# cryptostick-0v2.net
KiCad netlist of a schematic drawn in EAGLE
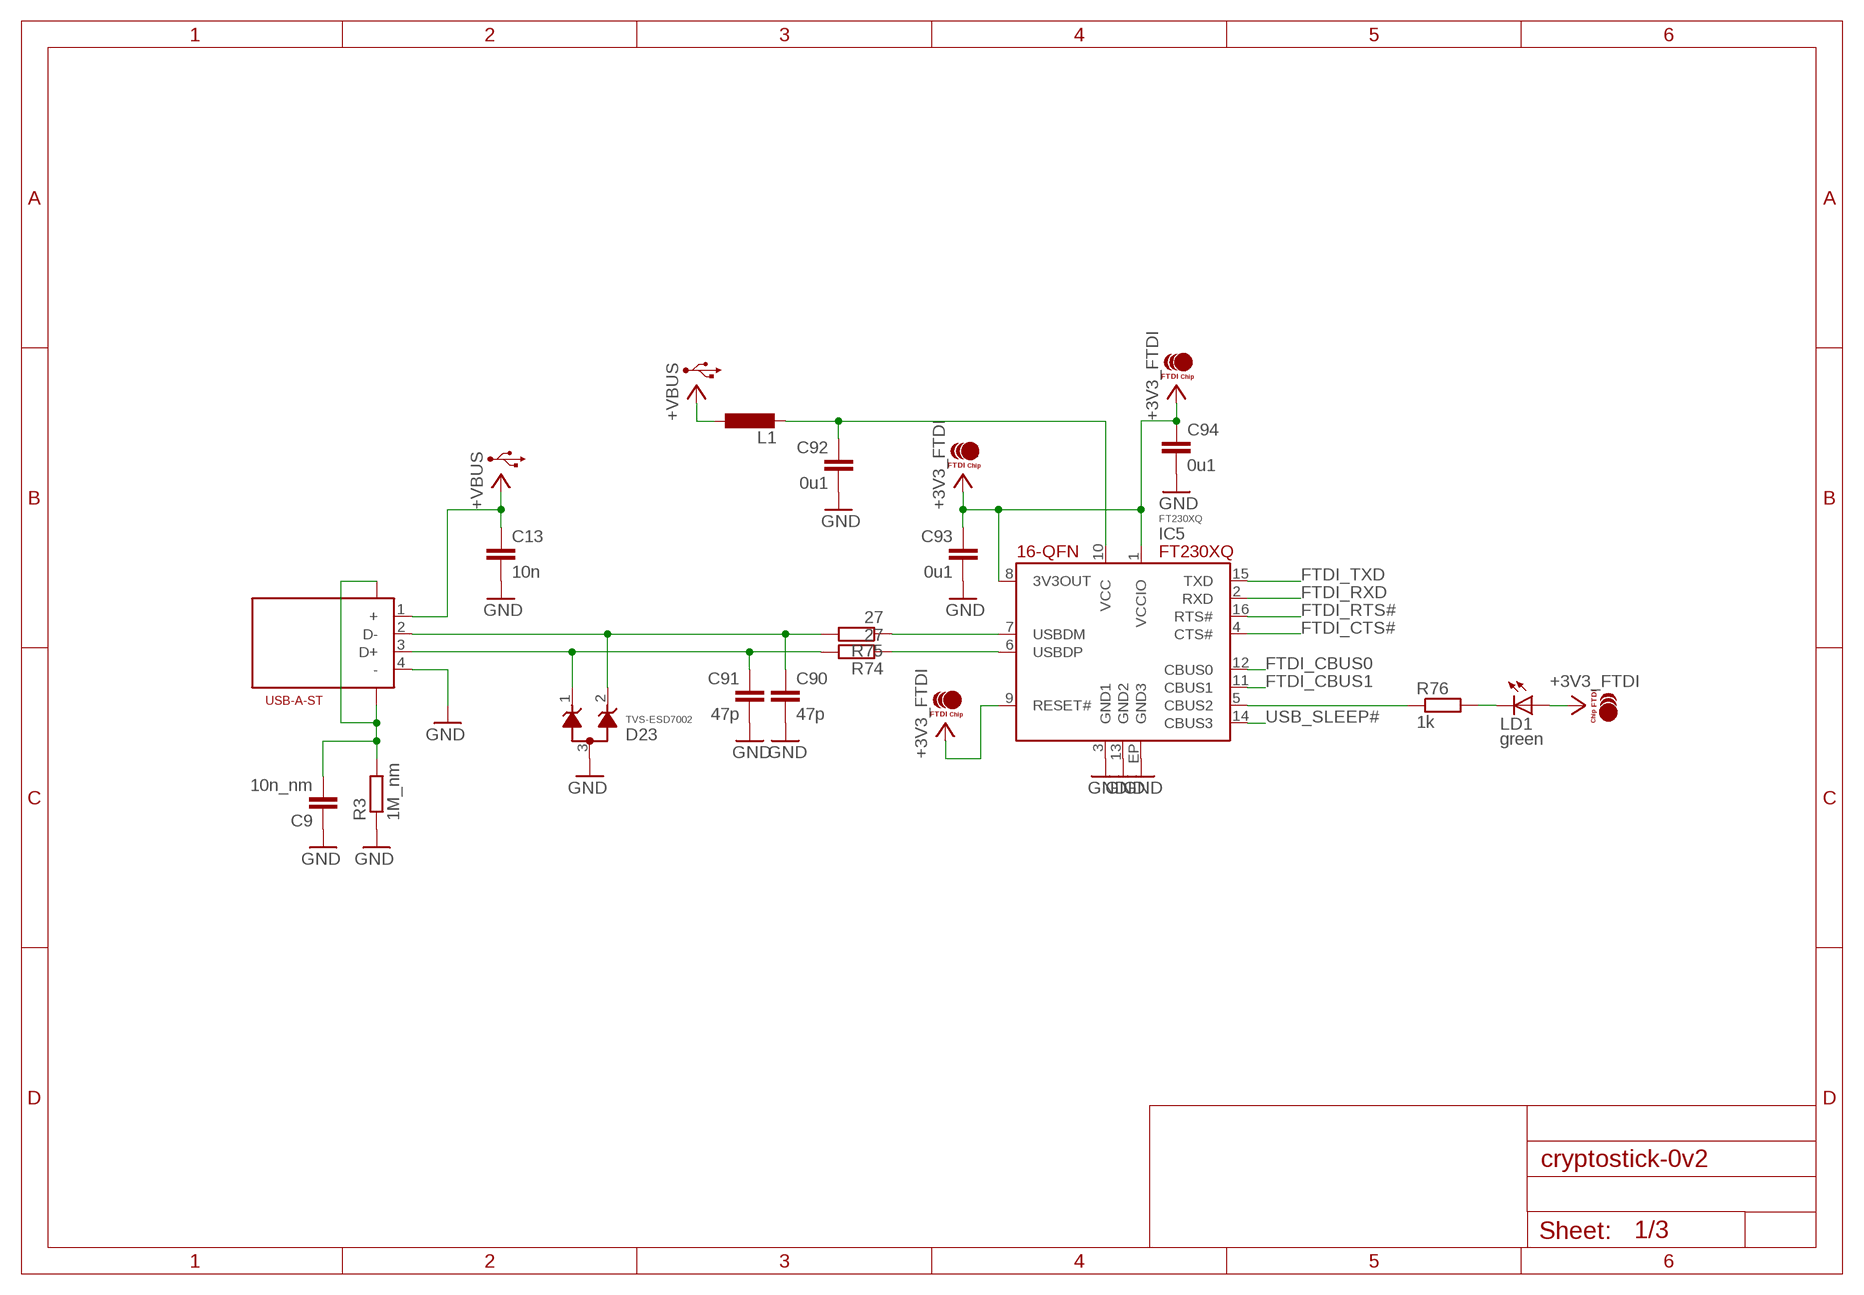
[diagram p0: schematic, sheet 1]
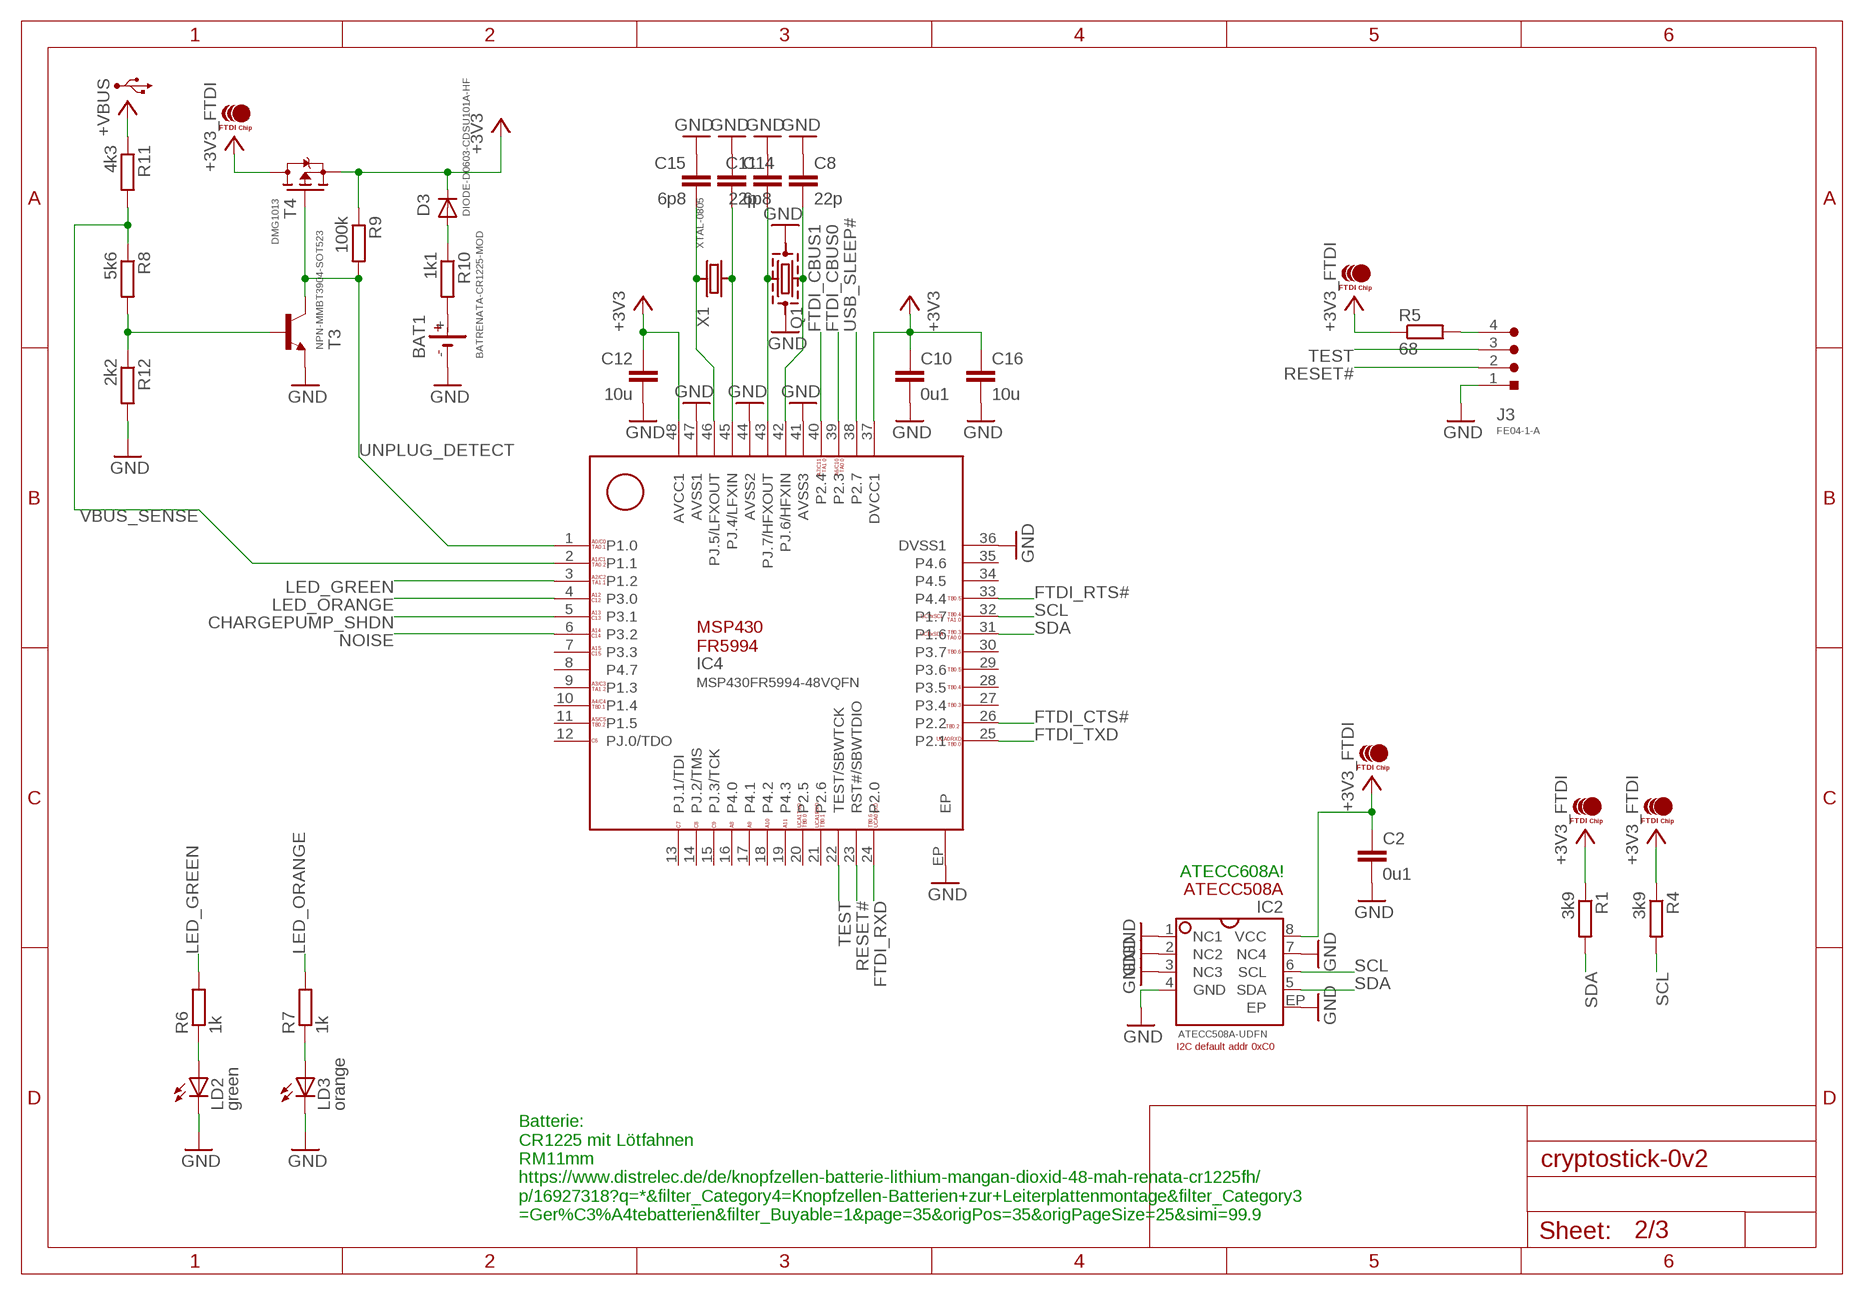
[diagram p1: schematic, sheet 2]
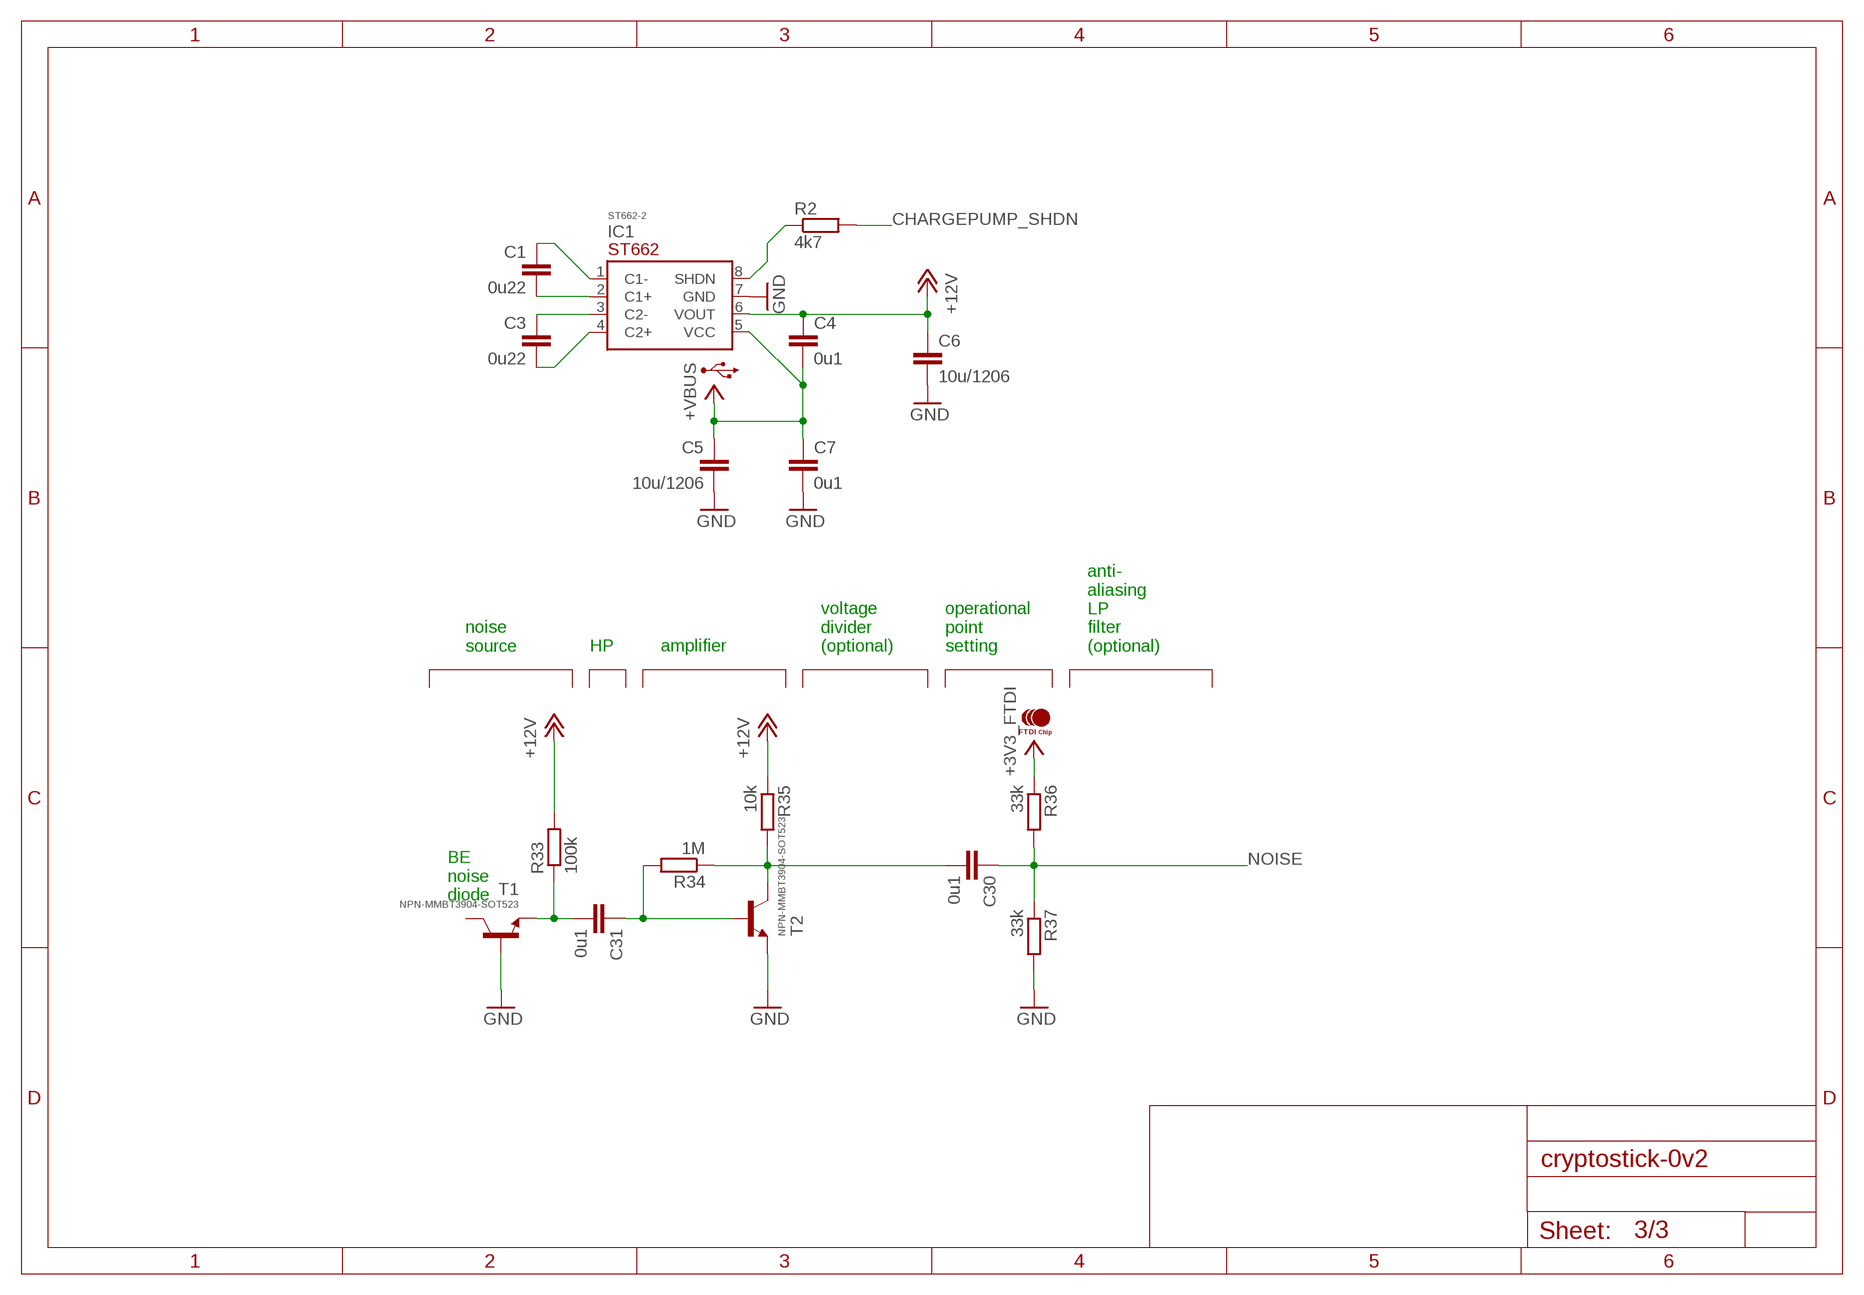
[diagram p2: schematic, sheet 3]

(export (version "E")
  (design (tool "Eeschema 10.0.6"))
  (components
    (comp (ref "C1")
      (value "0u22")
      (footprint "eagle-import:C0603")
      (libsource (lib "eagle-import") (part "C-EUC0603"))
    )
    (comp (ref "C3")
      (value "0u22")
      (footprint "eagle-import:C0603")
      (libsource (lib "eagle-import") (part "C-EUC0603"))
    )
    (comp (ref "C4")
      (value "0u1")
      (footprint "eagle-import:R0402-MCU")
      (libsource (lib "eagle-import") (part "C-EUR0402-MCU"))
    )
    (comp (ref "C5")
      (value "10u/1206")
      (footprint "eagle-import:C1206")
      (libsource (lib "eagle-import") (part "C-EUC1206"))
    )
    (comp (ref "C6")
      (value "10u/1206")
      (footprint "eagle-import:C1206")
      (libsource (lib "eagle-import") (part "C-EUC1206"))
    )
    (comp (ref "C7")
      (value "0u1")
      (footprint "eagle-import:R0402-MCU")
      (libsource (lib "eagle-import") (part "C-EUR0402-MCU"))
    )
    (comp (ref "C30")
      (value "0u1")
      (footprint "eagle-import:R0402-MCU")
      (libsource (lib "eagle-import") (part "C-EUR0402-MCU"))
    )
    (comp (ref "C31")
      (value "0u1")
      (footprint "eagle-import:R0402-MCU")
      (libsource (lib "eagle-import") (part "C-EUR0402-MCU"))
    )
    (comp (ref "IC1")
      (value "ST662-2")
      (footprint "eagle-import:8SOIC-2")
      (libsource (lib "eagle-import") (part "ST662-2"))
    )
    (comp (ref "R2")
      (value "4k7")
      (footprint "eagle-import:R0402-MCU")
      (libsource (lib "eagle-import") (part "R-EU_R0402-MCU"))
    )
    (comp (ref "R33")
      (value "100k")
      (footprint "eagle-import:R0402-MCU")
      (libsource (lib "eagle-import") (part "R-EU_R0402-MCU"))
    )
    (comp (ref "R34")
      (value "1M")
      (footprint "eagle-import:R0402-MCU")
      (libsource (lib "eagle-import") (part "R-EU_R0402-MCU"))
    )
    (comp (ref "R35")
      (value "10k")
      (footprint "eagle-import:R0402-MCU")
      (libsource (lib "eagle-import") (part "R-EU_R0402-MCU"))
    )
    (comp (ref "R36")
      (value "33k")
      (footprint "eagle-import:R0402-MCU")
      (libsource (lib "eagle-import") (part "R-EU_R0402-MCU"))
    )
    (comp (ref "R37")
      (value "33k")
      (footprint "eagle-import:R0402-MCU")
      (libsource (lib "eagle-import") (part "R-EU_R0402-MCU"))
    )
    (comp (ref "T1")
      (value "NPN-MMBT3904-SOT523")
      (footprint "eagle-import:SOT523")
      (libsource (lib "eagle-import") (part "NPN-MMBT3904-SOT523"))
    )
    (comp (ref "T2")
      (value "NPN-MMBT3904-SOT523")
      (footprint "eagle-import:SOT523")
      (libsource (lib "eagle-import") (part "NPN-MMBT3904-SOT523"))
    )
    (comp (ref "C9")
      (value "10n_nm")
      (footprint "eagle-import:C0603")
      (libsource (lib "eagle-import") (part "C-EUC0603"))
    )
    (comp (ref "C13")
      (value "10n")
      (footprint "eagle-import:R0402-MCU")
      (libsource (lib "eagle-import") (part "C-EUR0402-MCU"))
    )
    (comp (ref "C90")
      (value "47p")
      (footprint "eagle-import:R0402-MCU")
      (libsource (lib "eagle-import") (part "C-EUR0402-MCU"))
    )
    (comp (ref "C91")
      (value "47p")
      (footprint "eagle-import:R0402-MCU")
      (libsource (lib "eagle-import") (part "C-EUR0402-MCU"))
    )
    (comp (ref "C92")
      (value "0u1")
      (footprint "eagle-import:R0402-MCU")
      (libsource (lib "eagle-import") (part "C-EUR0402-MCU"))
    )
    (comp (ref "C93")
      (value "0u1")
      (footprint "eagle-import:R0402-MCU")
      (libsource (lib "eagle-import") (part "C-EUR0402-MCU"))
    )
    (comp (ref "C94")
      (value "0u1")
      (footprint "eagle-import:R0402-MCU")
      (libsource (lib "eagle-import") (part "C-EUR0402-MCU"))
    )
    (comp (ref "D23")
      (value "TVS-ESD7002")
      (footprint "eagle-import:SC70-3")
      (libsource (lib "eagle-import") (part "TVS-ESD7002"))
    )
    (comp (ref "IC5")
      (value "FT230XQ")
      (footprint "eagle-import:16QFN-FT230X")
      (libsource (lib "eagle-import") (part "FT230XQ"))
    )
    (comp (ref "J1")
      (value "USB-A-ST")
      (footprint "eagle-import:USB-A-ST")
      (libsource (lib "eagle-import") (part "USB-A-ST"))
    )
    (comp (ref "L1")
      (value "L-EUR0402-MCU")
      (footprint "eagle-import:R0402-MCU")
      (libsource (lib "eagle-import") (part "L-EUR0402-MCU"))
    )
    (comp (ref "LD1")
      (value "green")
      (footprint "eagle-import:0603-SIDELED-RPI")
      (libsource (lib "eagle-import") (part "LED-0603-SIDELED-RPI"))
    )
    (comp (ref "R3")
      (value "1M_nm")
      (footprint "eagle-import:R0603")
      (libsource (lib "eagle-import") (part "R-EU_R0603"))
    )
    (comp (ref "R74")
      (value "27")
      (footprint "eagle-import:R0402-MCU")
      (libsource (lib "eagle-import") (part "R-EU_R0402-MCU"))
    )
    (comp (ref "R75")
      (value "27")
      (footprint "eagle-import:R0402-MCU")
      (libsource (lib "eagle-import") (part "R-EU_R0402-MCU"))
    )
    (comp (ref "R76")
      (value "1k")
      (footprint "eagle-import:R0402-MCU")
      (libsource (lib "eagle-import") (part "R-EU_R0402-MCU"))
    )
    (comp (ref "BAT1")
      (value "BATRENATA-CR1225-MOD")
      (footprint "eagle-import:BAT-RENATA-CR1225-MOD")
      (libsource (lib "eagle-import") (part "BATRENATA-CR1225-MOD"))
    )
    (comp (ref "C2")
      (value "0u1")
      (footprint "eagle-import:R0402-MCU")
      (libsource (lib "eagle-import") (part "C-EUR0402-MCU"))
    )
    (comp (ref "C8")
      (value "22p")
      (footprint "eagle-import:R0402-MCU")
      (libsource (lib "eagle-import") (part "C-EUR0402-MCU"))
    )
    (comp (ref "C10")
      (value "0u1")
      (footprint "eagle-import:R0402-MCU")
      (libsource (lib "eagle-import") (part "C-EUR0402-MCU"))
    )
    (comp (ref "C11")
      (value "22p")
      (footprint "eagle-import:R0402-MCU")
      (libsource (lib "eagle-import") (part "C-EUR0402-MCU"))
    )
    (comp (ref "C12")
      (value "10u")
      (footprint "eagle-import:R0603-MCU")
      (libsource (lib "eagle-import") (part "C-EUR0603-MCU"))
    )
    (comp (ref "C14")
      (value "6p8")
      (footprint "eagle-import:R0402-MCU")
      (libsource (lib "eagle-import") (part "C-EUR0402-MCU"))
    )
    (comp (ref "C15")
      (value "6p8")
      (footprint "eagle-import:R0402-MCU")
      (libsource (lib "eagle-import") (part "C-EUR0402-MCU"))
    )
    (comp (ref "C16")
      (value "10u")
      (footprint "eagle-import:R0603-MCU")
      (libsource (lib "eagle-import") (part "C-EUR0603-MCU"))
    )
    (comp (ref "D3")
      (value "DIODE-D0603-CDSU101A-HF")
      (footprint "eagle-import:D-D0603")
      (libsource (lib "eagle-import") (part "DIODE-D0603"))
    )
    (comp (ref "IC2")
      (value "ATECC508A-UDFN")
      (footprint "eagle-import:8UDFN")
      (libsource (lib "eagle-import") (part "ATECC508A-UDFN"))
    )
    (comp (ref "IC4")
      (value "MSP430FR5994-48VQFN")
      (footprint "eagle-import:48VQFN-MSP430FR5994")
      (libsource (lib "eagle-import") (part "MSP430FR5994-48VQFN"))
    )
    (comp (ref "J3")
      (value "FE04-1-A")
      (footprint "eagle-import:FE04-1A")
      (libsource (lib "eagle-import") (part "FE04-1-A"))
    )
    (comp (ref "LD2")
      (value "green")
      (footprint "eagle-import:0603-SIDELED-RPI")
      (libsource (lib "eagle-import") (part "LED-0603-SIDELED-RPI"))
    )
    (comp (ref "LD3")
      (value "orange")
      (footprint "eagle-import:0603-SIDELED-RPI")
      (libsource (lib "eagle-import") (part "LED-0603-SIDELED-RPI"))
    )
    (comp (ref "Q1")
      (value "XTAL-2.0X1.6-MOD")
      (footprint "eagle-import:XTAL-2.0X1.6-MOD")
      (libsource (lib "eagle-import") (part "XTAL-2.0X1.6-MOD"))
    )
    (comp (ref "R1")
      (value "3k9")
      (footprint "eagle-import:R0402-MCU")
      (libsource (lib "eagle-import") (part "R-EU_R0402-MCU"))
    )
    (comp (ref "R4")
      (value "3k9")
      (footprint "eagle-import:R0402-MCU")
      (libsource (lib "eagle-import") (part "R-EU_R0402-MCU"))
    )
    (comp (ref "R5")
      (value "68")
      (footprint "eagle-import:R0402-MCU")
      (libsource (lib "eagle-import") (part "R-EU_R0402-MCU"))
    )
    (comp (ref "R6")
      (value "1k")
      (footprint "eagle-import:R0402-MCU")
      (libsource (lib "eagle-import") (part "R-EU_R0402-MCU"))
    )
    (comp (ref "R7")
      (value "1k")
      (footprint "eagle-import:R0402-MCU")
      (libsource (lib "eagle-import") (part "R-EU_R0402-MCU"))
    )
    (comp (ref "R8")
      (value "5k6")
      (footprint "eagle-import:R0402-MCU")
      (libsource (lib "eagle-import") (part "R-EU_R0402-MCU"))
    )
    (comp (ref "R9")
      (value "100k")
      (footprint "eagle-import:R0402-MCU")
      (libsource (lib "eagle-import") (part "R-EU_R0402-MCU"))
    )
    (comp (ref "R10")
      (value "1k1")
      (footprint "eagle-import:R0402-MCU")
      (libsource (lib "eagle-import") (part "R-EU_R0402-MCU"))
    )
    (comp (ref "R11")
      (value "4k3")
      (footprint "eagle-import:R0402-MCU")
      (libsource (lib "eagle-import") (part "R-EU_R0402-MCU"))
    )
    (comp (ref "R12")
      (value "2k2")
      (footprint "eagle-import:R0402-MCU")
      (libsource (lib "eagle-import") (part "R-EU_R0402-MCU"))
    )
    (comp (ref "T3")
      (value "NPN-MMBT3904-SOT523")
      (footprint "eagle-import:SOT523")
      (libsource (lib "eagle-import") (part "NPN-MMBT3904-SOT523"))
    )
    (comp (ref "T4")
      (value "DMG1013")
      (footprint "eagle-import:SC70-3")
      (libsource (lib "eagle-import") (part "P-MOSFET-SC70-3"))
    )
    (comp (ref "X1")
      (value "XTAL-0805")
      (footprint "eagle-import:XTAL-32KHZ-0805")
      (libsource (lib "eagle-import") (part "XTAL-0805"))
    )
  )
  (nets
    (net (code "1") (name "+3V3") (class "Default")
      (node (ref "C10") (pin "1") (pinfunction "1_1") (pintype "passive"))
      (node (ref "C12") (pin "1") (pinfunction "1_1") (pintype "passive"))
      (node (ref "C16") (pin "1") (pinfunction "1_1") (pintype "passive"))
      (node (ref "D3") (pin "C") (pinfunction "C_C") (pintype "bidirectional"))
      (node (ref "IC4") (pin "37") (pinfunction "DVCC1_37") (pintype "power_in"))
      (node (ref "IC4") (pin "48") (pinfunction "AVCC1_48") (pintype "power_in"))
      (node (ref "R9") (pin "1") (pinfunction "1_1") (pintype "passive"))
      (node (ref "T4") (pin "2") (pinfunction "S_2") (pintype "passive"))
    )
    (net (code "2") (name "+3V3_FTDI") (class "Default")
      (node (ref "C2") (pin "1") (pinfunction "1_1") (pintype "passive"))
      (node (ref "C93") (pin "1") (pinfunction "1_1") (pintype "passive"))
      (node (ref "C94") (pin "1") (pinfunction "1_1") (pintype "passive"))
      (node (ref "IC2") (pin "8") (pinfunction "VCC_8") (pintype "bidirectional"))
      (node (ref "IC5") (pin "1") (pinfunction "VCCIO_1") (pintype "bidirectional"))
      (node (ref "IC5") (pin "8") (pinfunction "3V3OUT_8") (pintype "bidirectional"))
      (node (ref "IC5") (pin "9") (pinfunction "RESET#_9") (pintype "bidirectional"))
      (node (ref "LD1") (pin "A") (pinfunction "A_A") (pintype "passive"))
      (node (ref "R1") (pin "1") (pinfunction "1_1") (pintype "passive"))
      (node (ref "R36") (pin "1") (pinfunction "1_1") (pintype "passive"))
      (node (ref "R4") (pin "1") (pinfunction "1_1") (pintype "passive"))
      (node (ref "R5") (pin "1") (pinfunction "1_1") (pintype "passive"))
      (node (ref "T4") (pin "3") (pinfunction "D_3") (pintype "passive"))
    )
    (net (code "3") (name "+12V") (class "Default")
      (node (ref "C4") (pin "1") (pinfunction "1_1") (pintype "passive"))
      (node (ref "C6") (pin "1") (pinfunction "1_1") (pintype "passive"))
      (node (ref "IC1") (pin "6") (pinfunction "VOUT_6") (pintype "bidirectional"))
      (node (ref "R33") (pin "2") (pinfunction "2_2") (pintype "passive"))
      (node (ref "R35") (pin "1") (pinfunction "1_1") (pintype "passive"))
    )
    (net (code "4") (name "+VBUS") (class "Default")
      (node (ref "C13") (pin "1") (pinfunction "1_1") (pintype "passive"))
      (node (ref "C4") (pin "2") (pinfunction "2_2") (pintype "passive"))
      (node (ref "C5") (pin "1") (pinfunction "1_1") (pintype "passive"))
      (node (ref "C7") (pin "1") (pinfunction "1_1") (pintype "passive"))
      (node (ref "IC1") (pin "5") (pinfunction "VCC_5") (pintype "bidirectional"))
      (node (ref "J1") (pin "1") (pinfunction "+_1") (pintype "bidirectional"))
      (node (ref "L1") (pin "1") (pinfunction "1_1") (pintype "passive"))
      (node (ref "R11") (pin "1") (pinfunction "1_1") (pintype "passive"))
    )
    (net (code "5") (name "CHARGEPUMP_SHDN") (class "Default")
      (node (ref "IC4") (pin "5") (pinfunction "P3.1_5") (pintype "bidirectional"))
      (node (ref "R2") (pin "2") (pinfunction "2_2") (pintype "passive"))
    )
    (net (code "6") (name "FTDI_CBUS0") (class "Default")
      (node (ref "IC4") (pin "39") (pinfunction "P2.3_39") (pintype "bidirectional"))
      (node (ref "IC5") (pin "12") (pinfunction "CBUS0_12") (pintype "bidirectional"))
    )
    (net (code "7") (name "FTDI_CBUS1") (class "Default")
      (node (ref "IC4") (pin "40") (pinfunction "P2.4_40") (pintype "bidirectional"))
      (node (ref "IC5") (pin "11") (pinfunction "CBUS1_11") (pintype "bidirectional"))
    )
    (net (code "8") (name "FTDI_CTS#") (class "Default")
      (node (ref "IC4") (pin "26") (pinfunction "P2.2_26") (pintype "bidirectional"))
      (node (ref "IC5") (pin "4") (pinfunction "CTS#_4") (pintype "bidirectional"))
    )
    (net (code "9") (name "FTDI_RTS#") (class "Default")
      (node (ref "IC4") (pin "33") (pinfunction "P4.4_33") (pintype "bidirectional"))
      (node (ref "IC5") (pin "16") (pinfunction "RTS#_16") (pintype "bidirectional"))
    )
    (net (code "10") (name "FTDI_RXD") (class "Default")
      (node (ref "IC4") (pin "24") (pinfunction "P2.0_24") (pintype "bidirectional"))
      (node (ref "IC5") (pin "2") (pinfunction "RXD_2") (pintype "bidirectional"))
    )
    (net (code "11") (name "FTDI_TXD") (class "Default")
      (node (ref "IC4") (pin "25") (pinfunction "P2.1_25") (pintype "bidirectional"))
      (node (ref "IC5") (pin "15") (pinfunction "TXD_15") (pintype "bidirectional"))
    )
    (net (code "12") (name "GND") (class "Default")
      (node (ref "BAT1") (pin "-") (pinfunction "-_-") (pintype "bidirectional"))
      (node (ref "C10") (pin "2") (pinfunction "2_2") (pintype "passive"))
      (node (ref "C11") (pin "1") (pinfunction "1_1") (pintype "passive"))
      (node (ref "C12") (pin "2") (pinfunction "2_2") (pintype "passive"))
      (node (ref "C13") (pin "2") (pinfunction "2_2") (pintype "passive"))
      (node (ref "C14") (pin "1") (pinfunction "1_1") (pintype "passive"))
      (node (ref "C15") (pin "1") (pinfunction "1_1") (pintype "passive"))
      (node (ref "C16") (pin "2") (pinfunction "2_2") (pintype "passive"))
      (node (ref "C2") (pin "2") (pinfunction "2_2") (pintype "passive"))
      (node (ref "C5") (pin "2") (pinfunction "2_2") (pintype "passive"))
      (node (ref "C6") (pin "2") (pinfunction "2_2") (pintype "passive"))
      (node (ref "C7") (pin "2") (pinfunction "2_2") (pintype "passive"))
      (node (ref "C8") (pin "1") (pinfunction "1_1") (pintype "passive"))
      (node (ref "C9") (pin "1") (pinfunction "1_1") (pintype "passive"))
      (node (ref "C90") (pin "2") (pinfunction "2_2") (pintype "passive"))
      (node (ref "C91") (pin "2") (pinfunction "2_2") (pintype "passive"))
      (node (ref "C92") (pin "2") (pinfunction "2_2") (pintype "passive"))
      (node (ref "C93") (pin "2") (pinfunction "2_2") (pintype "passive"))
      (node (ref "C94") (pin "2") (pinfunction "2_2") (pintype "passive"))
      (node (ref "D23") (pin "3") (pinfunction "3_3") (pintype "bidirectional"))
      (node (ref "IC1") (pin "7") (pinfunction "GND_7") (pintype "bidirectional"))
      (node (ref "IC2") (pin "1") (pinfunction "NC1_1") (pintype "bidirectional"))
      (node (ref "IC2") (pin "2") (pinfunction "NC2_2") (pintype "bidirectional"))
      (node (ref "IC2") (pin "3") (pinfunction "NC3_3") (pintype "bidirectional"))
      (node (ref "IC2") (pin "4") (pinfunction "GND_4") (pintype "bidirectional"))
      (node (ref "IC2") (pin "7") (pinfunction "NC4_7") (pintype "bidirectional"))
      (node (ref "IC2") (pin "EP") (pinfunction "EP_EP") (pintype "bidirectional"))
      (node (ref "IC4") (pin "36") (pinfunction "DVSS1_36") (pintype "power_in"))
      (node (ref "IC4") (pin "41") (pinfunction "AVSS3_41") (pintype "power_in"))
      (node (ref "IC4") (pin "44") (pinfunction "AVSS2_44") (pintype "power_in"))
      (node (ref "IC4") (pin "47") (pinfunction "AVSS1_47") (pintype "power_in"))
      (node (ref "IC4") (pin "EP") (pinfunction "EP_EP") (pintype "bidirectional"))
      (node (ref "IC5") (pin "13") (pinfunction "GND2_13") (pintype "bidirectional"))
      (node (ref "IC5") (pin "3") (pinfunction "GND1_3") (pintype "bidirectional"))
      (node (ref "IC5") (pin "EP") (pinfunction "GND3_EP") (pintype "bidirectional"))
      (node (ref "J1") (pin "4") (pinfunction "-_4") (pintype "bidirectional"))
      (node (ref "J3") (pin "1") (pinfunction "1_1") (pintype "bidirectional"))
      (node (ref "LD2") (pin "C") (pinfunction "C_C") (pintype "passive"))
      (node (ref "LD3") (pin "C") (pinfunction "C_C") (pintype "passive"))
      (node (ref "Q1") (pin "2") (pinfunction "GND1_2") (pintype "bidirectional"))
      (node (ref "Q1") (pin "4") (pinfunction "GND2_4") (pintype "bidirectional"))
      (node (ref "R12") (pin "2") (pinfunction "2_2") (pintype "passive"))
      (node (ref "R3") (pin "1") (pinfunction "1_1") (pintype "passive"))
      (node (ref "R37") (pin "2") (pinfunction "2_2") (pintype "passive"))
      (node (ref "T1") (pin "1") (pinfunction "B_1") (pintype "passive"))
      (node (ref "T2") (pin "2") (pinfunction "E_2") (pintype "passive"))
      (node (ref "T3") (pin "2") (pinfunction "E_2") (pintype "passive"))
    )
    (net (code "13") (name "LED_GREEN") (class "Default")
      (node (ref "IC4") (pin "3") (pinfunction "P1.2_3") (pintype "bidirectional"))
      (node (ref "R6") (pin "2") (pinfunction "2_2") (pintype "passive"))
    )
    (net (code "14") (name "LED_ORANGE") (class "Default")
      (node (ref "IC4") (pin "4") (pinfunction "P3.0_4") (pintype "bidirectional"))
      (node (ref "R7") (pin "2") (pinfunction "2_2") (pintype "passive"))
    )
    (net (code "15") (name "NOISE") (class "Default")
      (node (ref "C30") (pin "1") (pinfunction "1_1") (pintype "passive"))
      (node (ref "IC4") (pin "6") (pinfunction "P3.2_6") (pintype "bidirectional"))
      (node (ref "R36") (pin "2") (pinfunction "2_2") (pintype "passive"))
      (node (ref "R37") (pin "1") (pinfunction "1_1") (pintype "passive"))
    )
    (net (code "16") (name "Net-(BAT1-Pad+)") (class "Default")
      (node (ref "BAT1") (pin "+") (pinfunction "+_+") (pintype "bidirectional"))
      (node (ref "R10") (pin "2") (pinfunction "2_2") (pintype "passive"))
    )
    (net (code "17") (name "Net-(C9-Pad2)") (class "Default")
      (node (ref "C9") (pin "2") (pinfunction "2_2") (pintype "passive"))
      (node (ref "J1") (pin "SH1") (pinfunction "SH1_SH1") (pintype "bidirectional"))
      (node (ref "J1") (pin "SH2") (pinfunction "SH2_SH2") (pintype "bidirectional"))
      (node (ref "R3") (pin "2") (pinfunction "2_2") (pintype "passive"))
    )
    (net (code "18") (name "Net-(D3-PadA)") (class "Default")
      (node (ref "D3") (pin "A") (pinfunction "A_A") (pintype "bidirectional"))
      (node (ref "R10") (pin "1") (pinfunction "1_1") (pintype "passive"))
    )
    (net (code "19") (name "Net-(IC1-C1+)") (class "Default")
      (node (ref "C1") (pin "2") (pinfunction "2_2") (pintype "passive"))
      (node (ref "IC1") (pin "2") (pinfunction "C1+_2") (pintype "bidirectional"))
    )
    (net (code "20") (name "Net-(IC1-C1-)") (class "Default")
      (node (ref "C1") (pin "1") (pinfunction "1_1") (pintype "passive"))
      (node (ref "IC1") (pin "1") (pinfunction "C1-_1") (pintype "bidirectional"))
    )
    (net (code "21") (name "Net-(IC1-C2+)") (class "Default")
      (node (ref "C3") (pin "2") (pinfunction "2_2") (pintype "passive"))
      (node (ref "IC1") (pin "4") (pinfunction "C2+_4") (pintype "bidirectional"))
    )
    (net (code "22") (name "Net-(IC1-C2-)") (class "Default")
      (node (ref "C3") (pin "1") (pinfunction "1_1") (pintype "passive"))
      (node (ref "IC1") (pin "3") (pinfunction "C2-_3") (pintype "bidirectional"))
    )
    (net (code "23") (name "Net-(IC1-SHDN)") (class "Default")
      (node (ref "IC1") (pin "8") (pinfunction "SHDN_8") (pintype "bidirectional"))
      (node (ref "R2") (pin "1") (pinfunction "1_1") (pintype "passive"))
    )
    (net (code "24") (name "Net-(IC4-PJ.4{slash}LFXIN)") (class "Default")
      (node (ref "C14") (pin "2") (pinfunction "2_2") (pintype "passive"))
      (node (ref "IC4") (pin "45") (pinfunction "PJ.4/LFXIN_45") (pintype "bidirectional"))
      (node (ref "X1") (pin "P$1") (pinfunction "1_P$1") (pintype "bidirectional"))
    )
    (net (code "25") (name "Net-(IC4-PJ.5{slash}LFXOUT)") (class "Default")
      (node (ref "C15") (pin "2") (pinfunction "2_2") (pintype "passive"))
      (node (ref "IC4") (pin "46") (pinfunction "PJ.5/LFXOUT_46") (pintype "bidirectional"))
      (node (ref "X1") (pin "P$2") (pinfunction "2_P$2") (pintype "bidirectional"))
    )
    (net (code "26") (name "Net-(IC4-PJ.6{slash}HFXIN)") (class "Default")
      (node (ref "C8") (pin "2") (pinfunction "2_2") (pintype "passive"))
      (node (ref "IC4") (pin "42") (pinfunction "PJ.6/HFXIN_42") (pintype "bidirectional"))
      (node (ref "Q1") (pin "3") (pinfunction "2_3") (pintype "bidirectional"))
    )
    (net (code "27") (name "Net-(IC4-PJ.7{slash}HFXOUT)") (class "Default")
      (node (ref "C11") (pin "2") (pinfunction "2_2") (pintype "passive"))
      (node (ref "IC4") (pin "43") (pinfunction "PJ.7/HFXOUT_43") (pintype "bidirectional"))
      (node (ref "Q1") (pin "1") (pinfunction "1_1") (pintype "bidirectional"))
    )
    (net (code "28") (name "Net-(IC5-CBUS2)") (class "Default")
      (node (ref "IC5") (pin "5") (pinfunction "CBUS2_5") (pintype "bidirectional"))
      (node (ref "R76") (pin "1") (pinfunction "1_1") (pintype "passive"))
    )
    (net (code "29") (name "Net-(IC5-USBDM)") (class "Default")
      (node (ref "IC5") (pin "7") (pinfunction "USBDM_7") (pintype "bidirectional"))
      (node (ref "R75") (pin "1") (pinfunction "1_1") (pintype "passive"))
    )
    (net (code "30") (name "Net-(IC5-USBDP)") (class "Default")
      (node (ref "IC5") (pin "6") (pinfunction "USBDP_6") (pintype "bidirectional"))
      (node (ref "R74") (pin "1") (pinfunction "1_1") (pintype "passive"))
    )
    (net (code "31") (name "Net-(IC5-VCC)") (class "Default")
      (node (ref "C92") (pin "1") (pinfunction "1_1") (pintype "passive"))
      (node (ref "IC5") (pin "10") (pinfunction "VCC_10") (pintype "bidirectional"))
      (node (ref "L1") (pin "2") (pinfunction "2_2") (pintype "passive"))
    )
    (net (code "32") (name "Net-(J1-D+)") (class "Default")
      (node (ref "C91") (pin "1") (pinfunction "1_1") (pintype "passive"))
      (node (ref "D23") (pin "1") (pinfunction "1_1") (pintype "bidirectional"))
      (node (ref "J1") (pin "3") (pinfunction "D+_3") (pintype "bidirectional"))
      (node (ref "R74") (pin "2") (pinfunction "2_2") (pintype "passive"))
    )
    (net (code "33") (name "Net-(J1-D-)") (class "Default")
      (node (ref "C90") (pin "1") (pinfunction "1_1") (pintype "passive"))
      (node (ref "D23") (pin "2") (pinfunction "2_2") (pintype "bidirectional"))
      (node (ref "J1") (pin "2") (pinfunction "D-_2") (pintype "bidirectional"))
      (node (ref "R75") (pin "2") (pinfunction "2_2") (pintype "passive"))
    )
    (net (code "34") (name "Net-(J3-Pad4)") (class "Default")
      (node (ref "J3") (pin "4") (pinfunction "4_4") (pintype "bidirectional"))
      (node (ref "R5") (pin "2") (pinfunction "2_2") (pintype "passive"))
    )
    (net (code "35") (name "Net-(LD1-PadC)") (class "Default")
      (node (ref "LD1") (pin "C") (pinfunction "C_C") (pintype "passive"))
      (node (ref "R76") (pin "2") (pinfunction "2_2") (pintype "passive"))
    )
    (net (code "36") (name "Net-(LD2-PadA)") (class "Default")
      (node (ref "LD2") (pin "A") (pinfunction "A_A") (pintype "passive"))
      (node (ref "R6") (pin "1") (pinfunction "1_1") (pintype "passive"))
    )
    (net (code "37") (name "Net-(LD3-PadA)") (class "Default")
      (node (ref "LD3") (pin "A") (pinfunction "A_A") (pintype "passive"))
      (node (ref "R7") (pin "1") (pinfunction "1_1") (pintype "passive"))
    )
    (net (code "38") (name "Net-(T1-E)") (class "Default")
      (node (ref "C31") (pin "2") (pinfunction "2_2") (pintype "passive"))
      (node (ref "R33") (pin "1") (pinfunction "1_1") (pintype "passive"))
      (node (ref "T1") (pin "2") (pinfunction "E_2") (pintype "passive"))
    )
    (net (code "39") (name "Net-(T2-B)") (class "Default")
      (node (ref "C31") (pin "1") (pinfunction "1_1") (pintype "passive"))
      (node (ref "R34") (pin "2") (pinfunction "2_2") (pintype "passive"))
      (node (ref "T2") (pin "1") (pinfunction "B_1") (pintype "passive"))
    )
    (net (code "40") (name "Net-(T2-C)") (class "Default")
      (node (ref "C30") (pin "2") (pinfunction "2_2") (pintype "passive"))
      (node (ref "R34") (pin "1") (pinfunction "1_1") (pintype "passive"))
      (node (ref "R35") (pin "2") (pinfunction "2_2") (pintype "passive"))
      (node (ref "T2") (pin "3") (pinfunction "C_3") (pintype "passive"))
    )
    (net (code "41") (name "Net-(T3-B)") (class "Default")
      (node (ref "R12") (pin "1") (pinfunction "1_1") (pintype "passive"))
      (node (ref "R8") (pin "2") (pinfunction "2_2") (pintype "passive"))
      (node (ref "T3") (pin "1") (pinfunction "B_1") (pintype "passive"))
    )
    (net (code "42") (name "RESET#") (class "Default")
      (node (ref "IC4") (pin "23") (pinfunction "RST#/SBWTDIO_23") (pintype "bidirectional"))
      (node (ref "J3") (pin "2") (pinfunction "2_2") (pintype "bidirectional"))
    )
    (net (code "43") (name "SCL") (class "Default")
      (node (ref "IC2") (pin "6") (pinfunction "SCL_6") (pintype "bidirectional"))
      (node (ref "IC4") (pin "32") (pinfunction "P1.7_32") (pintype "bidirectional"))
      (node (ref "R4") (pin "2") (pinfunction "2_2") (pintype "passive"))
    )
    (net (code "44") (name "SDA") (class "Default")
      (node (ref "IC2") (pin "5") (pinfunction "SDA_5") (pintype "bidirectional"))
      (node (ref "IC4") (pin "31") (pinfunction "P1.6_31") (pintype "bidirectional"))
      (node (ref "R1") (pin "2") (pinfunction "2_2") (pintype "passive"))
    )
    (net (code "45") (name "TEST") (class "Default")
      (node (ref "IC4") (pin "22") (pinfunction "TEST/SBWTCK_22") (pintype "bidirectional"))
      (node (ref "J3") (pin "3") (pinfunction "3_3") (pintype "bidirectional"))
    )
    (net (code "46") (name "UNPLUG_DETECT") (class "Default")
      (node (ref "IC4") (pin "1") (pinfunction "P1.0_1") (pintype "bidirectional"))
      (node (ref "R9") (pin "2") (pinfunction "2_2") (pintype "passive"))
      (node (ref "T3") (pin "3") (pinfunction "C_3") (pintype "passive"))
      (node (ref "T4") (pin "1") (pinfunction "G_1") (pintype "passive"))
    )
    (net (code "47") (name "USB_SLEEP#") (class "Default")
      (node (ref "IC4") (pin "38") (pinfunction "P2.7_38") (pintype "bidirectional"))
      (node (ref "IC5") (pin "14") (pinfunction "CBUS3_14") (pintype "bidirectional"))
    )
    (net (code "48") (name "VBUS_SENSE") (class "Default")
      (node (ref "IC4") (pin "2") (pinfunction "P1.1_2") (pintype "bidirectional"))
      (node (ref "R11") (pin "2") (pinfunction "2_2") (pintype "passive"))
      (node (ref "R8") (pin "1") (pinfunction "1_1") (pintype "passive"))
    )
    (net (code "49") (name "unconnected-(IC4-P1.3-Pad9)") (class "Default")
      (node (ref "IC4") (pin "9") (pinfunction "P1.3_9") (pintype "bidirectional"))
    )
    (net (code "50") (name "unconnected-(IC4-P1.4-Pad10)") (class "Default")
      (node (ref "IC4") (pin "10") (pinfunction "P1.4_10") (pintype "bidirectional"))
    )
    (net (code "51") (name "unconnected-(IC4-P1.5-Pad11)") (class "Default")
      (node (ref "IC4") (pin "11") (pinfunction "P1.5_11") (pintype "bidirectional"))
    )
    (net (code "52") (name "unconnected-(IC4-P2.5-Pad20)") (class "Default")
      (node (ref "IC4") (pin "20") (pinfunction "P2.5_20") (pintype "bidirectional"))
    )
    (net (code "53") (name "unconnected-(IC4-P2.6-Pad21)") (class "Default")
      (node (ref "IC4") (pin "21") (pinfunction "P2.6_21") (pintype "bidirectional"))
    )
    (net (code "54") (name "unconnected-(IC4-P3.3-Pad7)") (class "Default")
      (node (ref "IC4") (pin "7") (pinfunction "P3.3_7") (pintype "bidirectional"))
    )
    (net (code "55") (name "unconnected-(IC4-P3.4-Pad27)") (class "Default")
      (node (ref "IC4") (pin "27") (pinfunction "P3.4_27") (pintype "bidirectional"))
    )
    (net (code "56") (name "unconnected-(IC4-P3.5-Pad28)") (class "Default")
      (node (ref "IC4") (pin "28") (pinfunction "P3.5_28") (pintype "bidirectional"))
    )
    (net (code "57") (name "unconnected-(IC4-P3.6-Pad29)") (class "Default")
      (node (ref "IC4") (pin "29") (pinfunction "P3.6_29") (pintype "bidirectional"))
    )
    (net (code "58") (name "unconnected-(IC4-P3.7-Pad30)") (class "Default")
      (node (ref "IC4") (pin "30") (pinfunction "P3.7_30") (pintype "bidirectional"))
    )
    (net (code "59") (name "unconnected-(IC4-P4.0-Pad16)") (class "Default")
      (node (ref "IC4") (pin "16") (pinfunction "P4.0_16") (pintype "bidirectional"))
    )
    (net (code "60") (name "unconnected-(IC4-P4.1-Pad17)") (class "Default")
      (node (ref "IC4") (pin "17") (pinfunction "P4.1_17") (pintype "bidirectional"))
    )
    (net (code "61") (name "unconnected-(IC4-P4.2-Pad18)") (class "Default")
      (node (ref "IC4") (pin "18") (pinfunction "P4.2_18") (pintype "bidirectional"))
    )
    (net (code "62") (name "unconnected-(IC4-P4.3-Pad19)") (class "Default")
      (node (ref "IC4") (pin "19") (pinfunction "P4.3_19") (pintype "bidirectional"))
    )
    (net (code "63") (name "unconnected-(IC4-P4.5-Pad34)") (class "Default")
      (node (ref "IC4") (pin "34") (pinfunction "P4.5_34") (pintype "bidirectional"))
    )
    (net (code "64") (name "unconnected-(IC4-P4.6-Pad35)") (class "Default")
      (node (ref "IC4") (pin "35") (pinfunction "P4.6_35") (pintype "bidirectional"))
    )
    (net (code "65") (name "unconnected-(IC4-P4.7-Pad8)") (class "Default")
      (node (ref "IC4") (pin "8") (pinfunction "P4.7_8") (pintype "bidirectional"))
    )
    (net (code "66") (name "unconnected-(IC4-PJ.0{slash}TDO-Pad12)") (class "Default")
      (node (ref "IC4") (pin "12") (pinfunction "PJ.0/TDO_12") (pintype "bidirectional"))
    )
    (net (code "67") (name "unconnected-(IC4-PJ.1{slash}TDI-Pad13)") (class "Default")
      (node (ref "IC4") (pin "13") (pinfunction "PJ.1/TDI_13") (pintype "bidirectional"))
    )
    (net (code "68") (name "unconnected-(IC4-PJ.2{slash}TMS-Pad14)") (class "Default")
      (node (ref "IC4") (pin "14") (pinfunction "PJ.2/TMS_14") (pintype "bidirectional"))
    )
    (net (code "69") (name "unconnected-(IC4-PJ.3{slash}TCK-Pad15)") (class "Default")
      (node (ref "IC4") (pin "15") (pinfunction "PJ.3/TCK_15") (pintype "bidirectional"))
    )
    (net (code "70") (name "unconnected-(T1-C-Pad3)") (class "Default")
      (node (ref "T1") (pin "3") (pinfunction "C_3") (pintype "passive"))
    )
  )
)
